# P6_V5.net
KiCad netlist of a schematic drawn in EAGLE
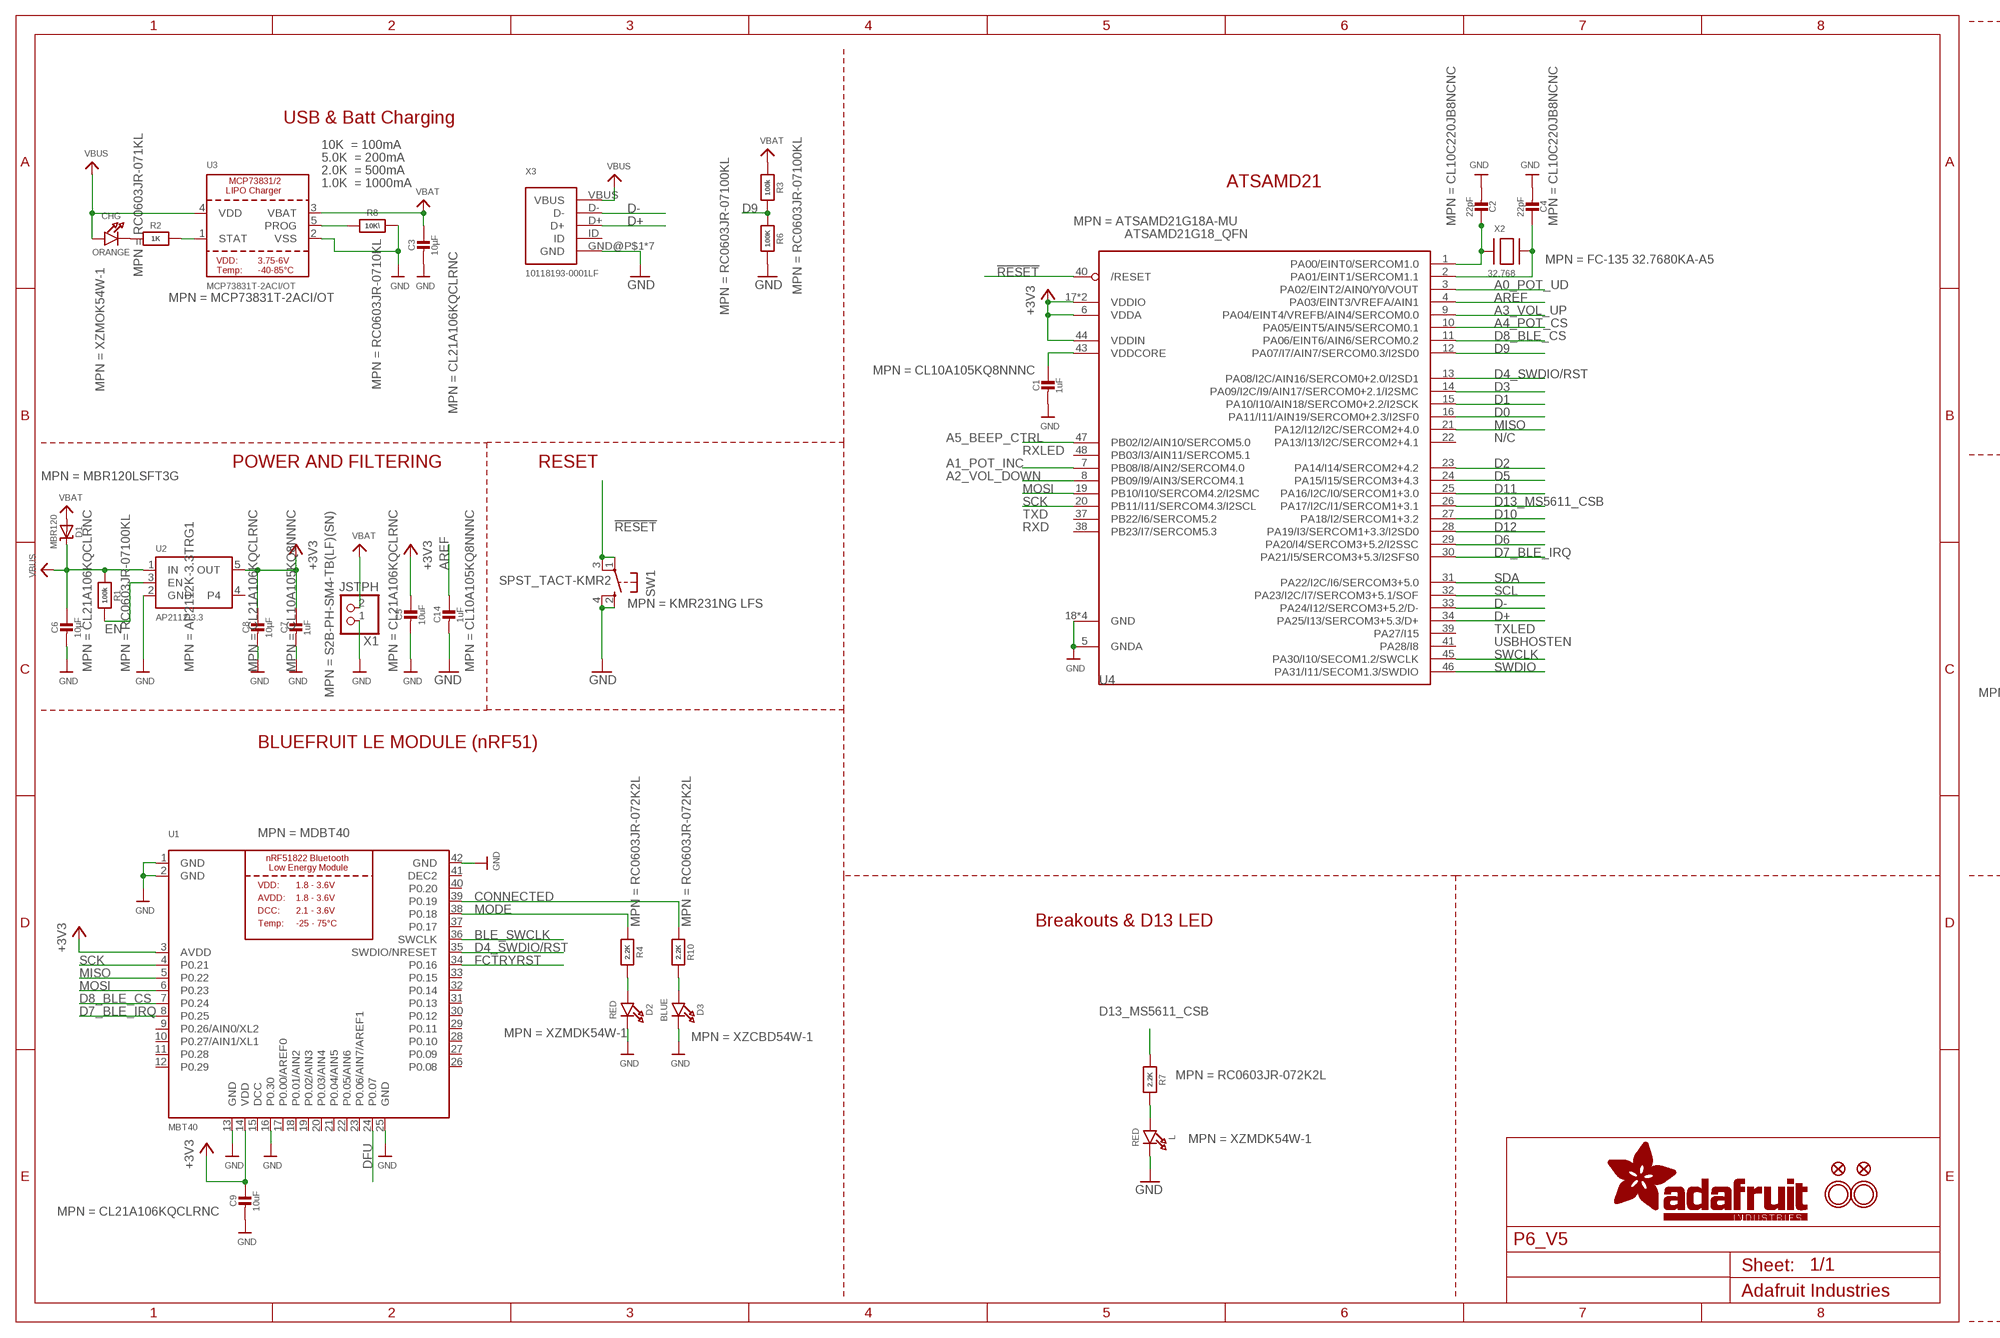
[diagram p0: schematic, sheet 1, part 1 of 2]
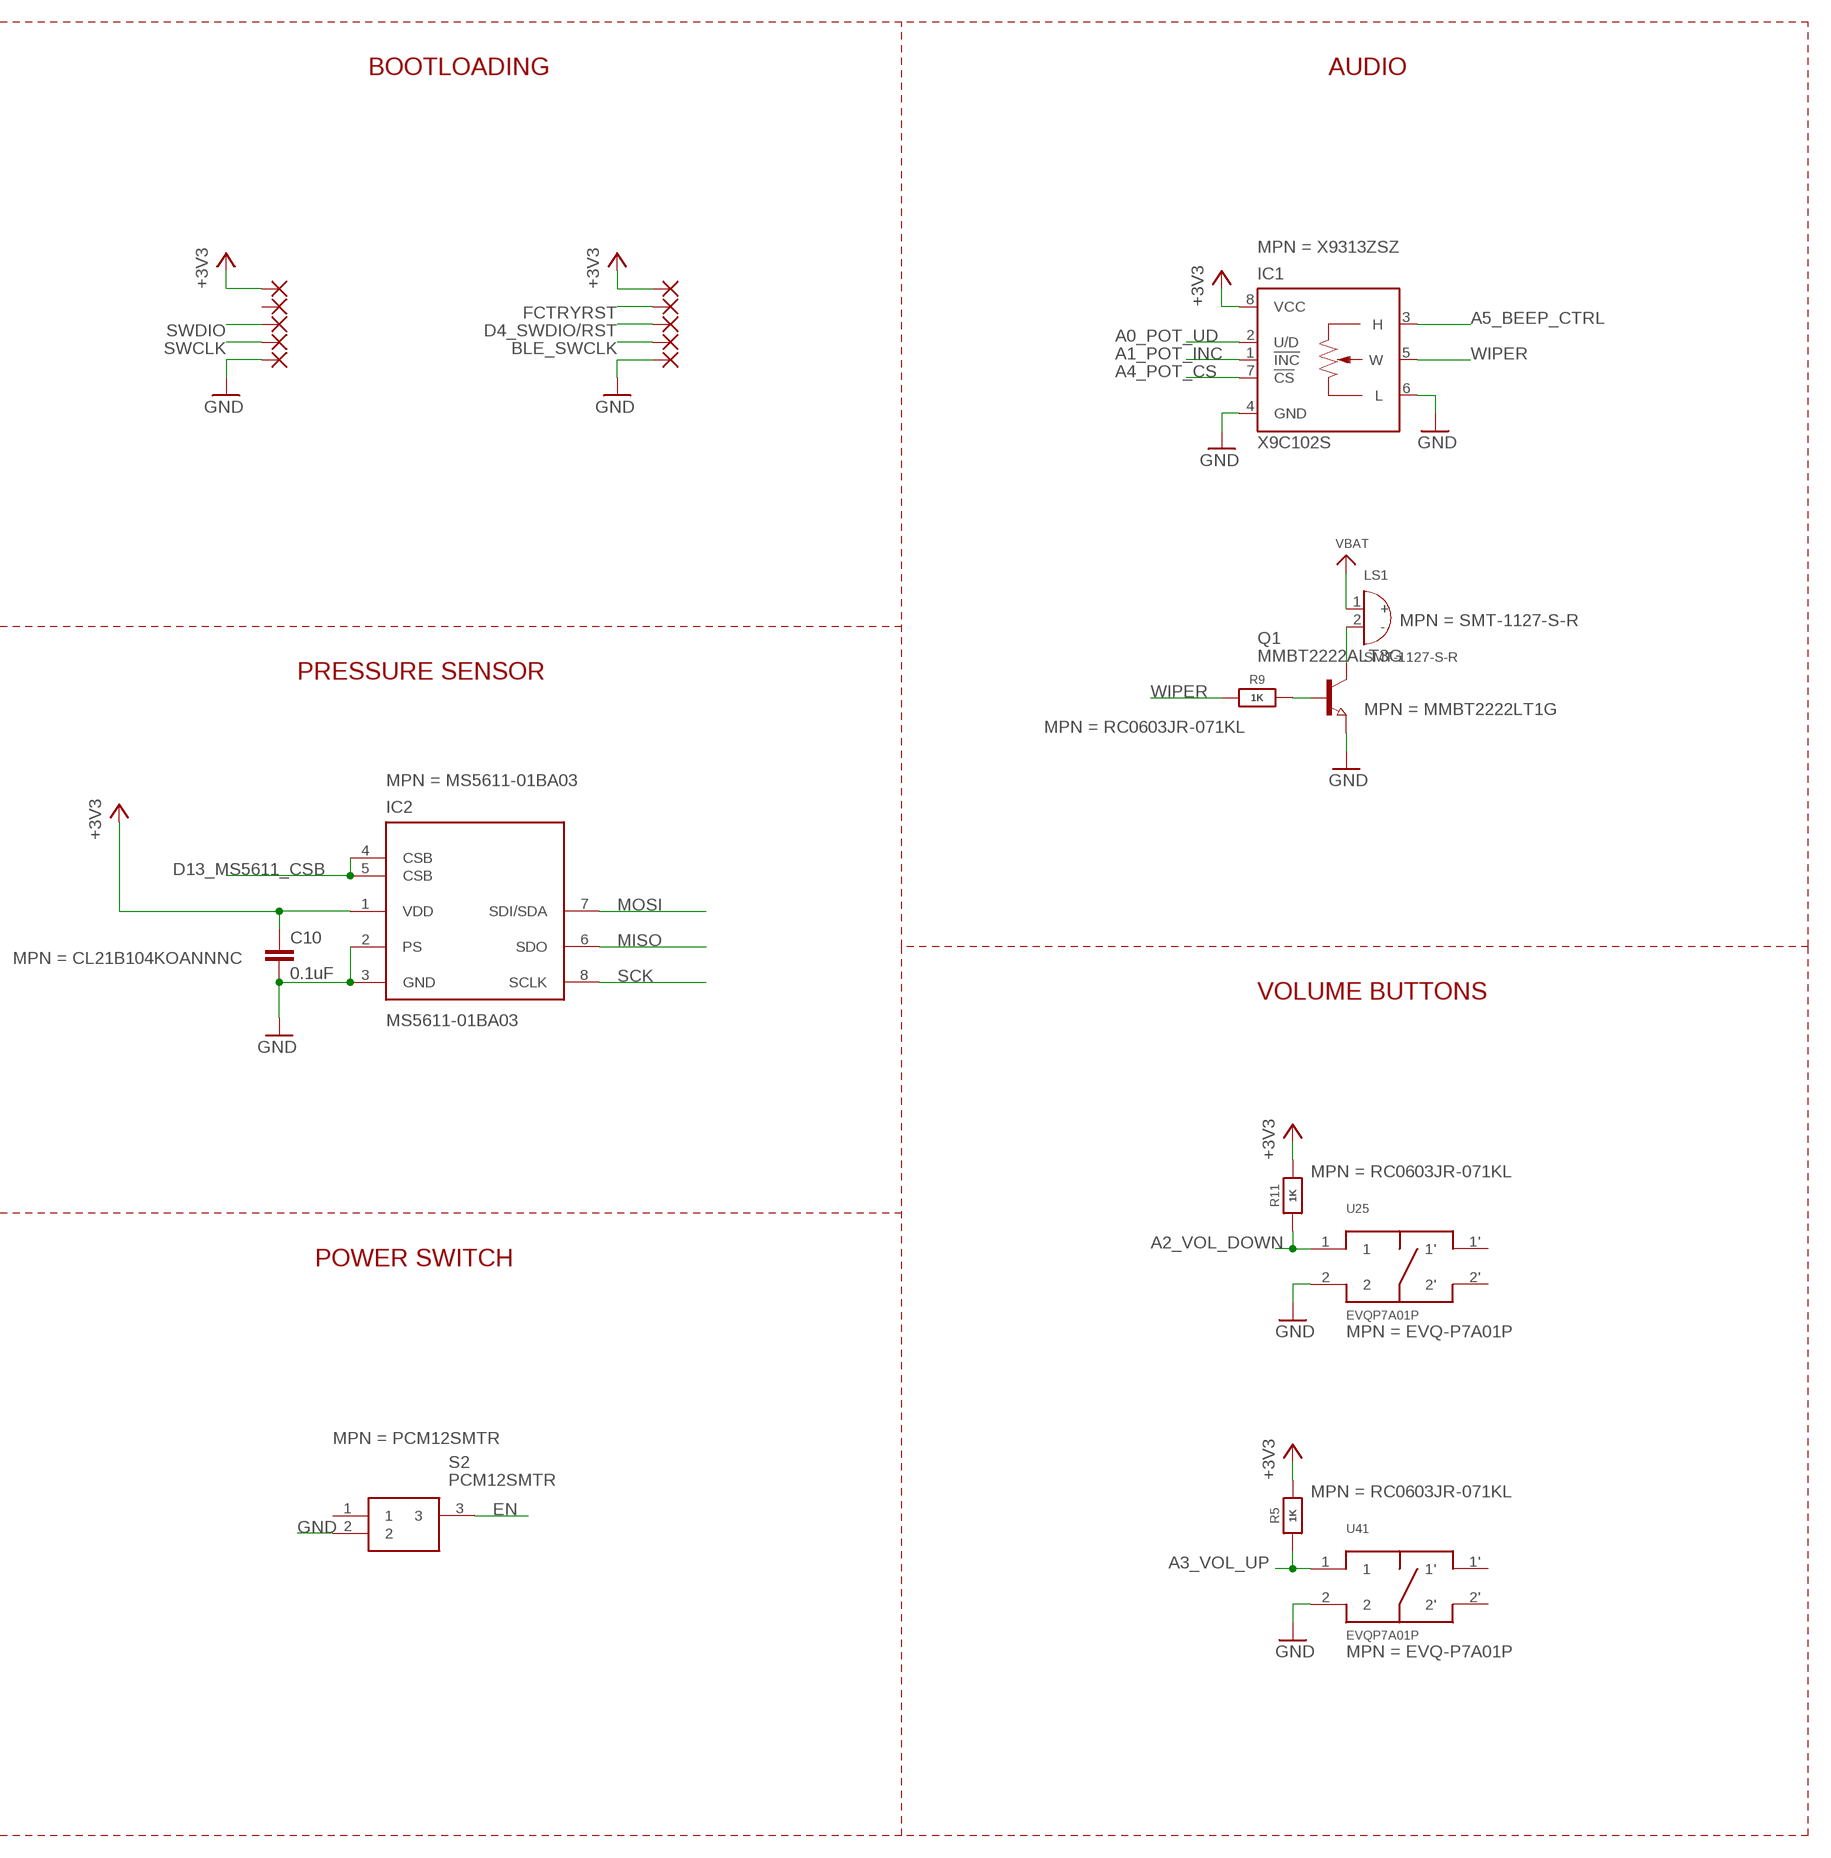
[diagram p1: schematic, sheet 1, part 2 of 2]

(export (version "E")
  (design (tool "Eeschema 10.0.6"))
  (components
    (comp (ref "C1")
      (value "1uF")
      (footprint "eagle-import:0603-NO")
      (fields (field (name "MPN") "CL10A105KQ8NNNC"))
      (libsource (lib "eagle-import") (part "CAP_CERAMIC0603_NO"))
    )
    (comp (ref "C2")
      (value "22pF")
      (footprint "eagle-import:0603-NO")
      (fields (field (name "MPN") "CL10C220JB8NCNC"))
      (libsource (lib "eagle-import") (part "CAP_CERAMIC0603_NO"))
    )
    (comp (ref "C3")
      (value "10µF")
      (footprint "eagle-import:0805-NO")
      (fields (field (name "MPN") "CL21A106KQCLRNC"))
      (libsource (lib "eagle-import") (part "CAP_CERAMIC0805-NOOUTLINE"))
    )
    (comp (ref "C4")
      (value "22pF")
      (footprint "eagle-import:0603-NO")
      (fields (field (name "MPN") "CL10C220JB8NCNC"))
      (libsource (lib "eagle-import") (part "CAP_CERAMIC0603_NO"))
    )
    (comp (ref "C5")
      (value "10uF")
      (footprint "eagle-import:0805-NO")
      (fields (field (name "MPN") "CL21A106KQCLRNC"))
      (libsource (lib "eagle-import") (part "CAP_CERAMIC0805-NOOUTLINE"))
    )
    (comp (ref "C6")
      (value "10µF")
      (footprint "eagle-import:0805-NO")
      (fields (field (name "MPN") "CL21A106KQCLRNC"))
      (libsource (lib "eagle-import") (part "CAP_CERAMIC0805-NOOUTLINE"))
    )
    (comp (ref "C7")
      (value "1uF")
      (footprint "eagle-import:0603-NO")
      (fields (field (name "MPN") "CL10A105KQ8NNNC"))
      (libsource (lib "eagle-import") (part "CAP_CERAMIC0603_NO"))
    )
    (comp (ref "C8")
      (value "10µF")
      (footprint "eagle-import:0805-NO")
      (fields (field (name "MPN") "CL21A106KQCLRNC"))
      (libsource (lib "eagle-import") (part "CAP_CERAMIC0805-NOOUTLINE"))
    )
    (comp (ref "C9")
      (value "10uF")
      (footprint "eagle-import:0805-NO")
      (fields (field (name "MPN") "CL21A106KQCLRNC"))
      (libsource (lib "eagle-import") (part "CAP_CERAMIC0805-NOOUTLINE"))
    )
    (comp (ref "C10")
      (value "0.1uF")
      (footprint "eagle-import:C0805K")
      (fields (field (name "MPN") "CL21B104KOANNNC"))
      (libsource (lib "eagle-import") (part "C-EUC0805K"))
    )
    (comp (ref "C14")
      (value "1uF")
      (footprint "eagle-import:0603-NO")
      (fields (field (name "MPN") "CL10A105KQ8NNNC"))
      (libsource (lib "eagle-import") (part "CAP_CERAMIC0603_NO"))
    )
    (comp (ref "CHG")
      (value "ORANGE")
      (footprint "eagle-import:CHIPLED_0805_NOOUTLINE")
      (fields (field (name "MPN") "XZMOK54W-1"))
      (libsource (lib "eagle-import") (part "LED0805_NOOUTLINE"))
    )
    (comp (ref "D1")
      (value "MBR120")
      (footprint "eagle-import:SOD-123")
      (fields (field (name "MPN") "MBR120LSFT3G"))
      (libsource (lib "eagle-import") (part "DIODE-SCHOTTKYSOD-123"))
    )
    (comp (ref "D2")
      (value "RED")
      (footprint "eagle-import:CHIPLED_0805_NOOUTLINE")
      (fields (field (name "MPN") "XZMDK54W-1"))
      (libsource (lib "eagle-import") (part "LED0805_NOOUTLINE"))
    )
    (comp (ref "D3")
      (value "BLUE")
      (footprint "eagle-import:CHIPLED_0805_NOOUTLINE")
      (fields (field (name "MPN") "XZCBD54W-1"))
      (libsource (lib "eagle-import") (part "LED0805_NOOUTLINE"))
    )
    (comp (ref "IC1")
      (value "X9C102S")
      (footprint "eagle-import:SOIC08")
      (fields
        (field (name "MF") "INTERSIL")
        (field (name "MPN") "X9C102SIZ")
        (field (name "MPN_1") "X9313ZSZ")
      )
      (libsource (lib "eagle-import") (part "X9C102S"))
    )
    (comp (ref "IC2")
      (value "MS5611-01BA03")
      (footprint "eagle-import:SON125P300X500X100-8N")
      (fields (field (name "MPN") "MS5611-01BA03"))
      (libsource (lib "eagle-import") (part "MS5611-01BA03UNO"))
    )
    (comp (ref "L")
      (value "RED")
      (footprint "eagle-import:CHIPLED_0805_NOOUTLINE")
      (fields (field (name "MPN") "XZMDK54W-1"))
      (libsource (lib "eagle-import") (part "LED0805_NOOUTLINE"))
    )
    (comp (ref "LS1")
      (value "SMT-1127-S-R")
      (footprint "eagle-import:XDCR_SMT-1127-S-R")
      (description "Black Passive Electromagnetic SMD Buzzer 3V 80mA 2700Hz 92dB 9x3.2mm")
      (fields
        (field (name "MF") "PUI Audio")
        (field (name "MP") "BOT-03D-BUJEON, SMT-1127-S-R")
        (field (name "MPN") "SMT-1127-S-R")
      )
      (libsource (lib "eagle-import") (part "SMT-1127-S-R"))
    )
    (comp (ref "PAD1")
      (value "1,6/0,8")
      (footprint "eagle-import:1,6_0,8")
      (libsource (lib "eagle-import") (part "1,6/0,8"))
    )
    (comp (ref "PAD2")
      (value "1,6/0,8")
      (footprint "eagle-import:1,6_0,8")
      (libsource (lib "eagle-import") (part "1,6/0,8"))
    )
    (comp (ref "PAD3")
      (value "1,6/0,8")
      (footprint "eagle-import:1,6_0,8")
      (libsource (lib "eagle-import") (part "1,6/0,8"))
    )
    (comp (ref "PAD4")
      (value "1,6/0,8")
      (footprint "eagle-import:1,6_0,8")
      (libsource (lib "eagle-import") (part "1,6/0,8"))
    )
    (comp (ref "PAD5")
      (value "1,6/0,8")
      (footprint "eagle-import:1,6_0,8")
      (libsource (lib "eagle-import") (part "1,6/0,8"))
    )
    (comp (ref "PAD6")
      (value "1,6/0,8")
      (footprint "eagle-import:1,6_0,8")
      (libsource (lib "eagle-import") (part "1,6/0,8"))
    )
    (comp (ref "PAD7")
      (value "1,6/0,8")
      (footprint "eagle-import:1,6_0,8")
      (libsource (lib "eagle-import") (part "1,6/0,8"))
    )
    (comp (ref "PAD8")
      (value "1,6/0,8")
      (footprint "eagle-import:1,6_0,8")
      (libsource (lib "eagle-import") (part "1,6/0,8"))
    )
    (comp (ref "PAD9")
      (value "1,6/0,8")
      (footprint "eagle-import:1,6_0,8")
      (libsource (lib "eagle-import") (part "1,6/0,8"))
    )
    (comp (ref "PAD10")
      (value "1,6/0,8")
      (footprint "eagle-import:1,6_0,8")
      (libsource (lib "eagle-import") (part "1,6/0,8"))
    )
    (comp (ref "Q1")
      (value "MMBT2222ALT3G")
      (footprint "eagle-import:SOT23")
      (fields (field (name "MPN") "MMBT2222LT1G"))
      (libsource (lib "eagle-import") (part "NPN-TRANSISTOR_SOT23"))
    )
    (comp (ref "R1")
      (value "100k")
      (footprint "eagle-import:0603-NO")
      (fields (field (name "MPN") "RC0603JR-07100KL"))
      (libsource (lib "eagle-import") (part "RESISTOR_0603_NOOUT"))
    )
    (comp (ref "R2")
      (value "1K")
      (footprint "eagle-import:0603-NO")
      (fields (field (name "MPN") "RC0603JR-071KL"))
      (libsource (lib "eagle-import") (part "RESISTOR_0603_NOOUT"))
    )
    (comp (ref "R3")
      (value "100k")
      (footprint "eagle-import:0603-NO")
      (fields (field (name "MPN") "RC0603JR-07100KL"))
      (libsource (lib "eagle-import") (part "RESISTOR_0603_NOOUT"))
    )
    (comp (ref "R4")
      (value "2.2K")
      (footprint "eagle-import:0603-NO")
      (fields (field (name "MPN") "RC0603JR-072K2L"))
      (libsource (lib "eagle-import") (part "RESISTOR_0603_NOOUT"))
    )
    (comp (ref "R5")
      (value "1K")
      (footprint "eagle-import:0603-NO")
      (fields (field (name "MPN") "RC0603JR-071KL"))
      (libsource (lib "eagle-import") (part "RESISTOR_0603_NOOUT"))
    )
    (comp (ref "R6")
      (value "100K")
      (footprint "eagle-import:0603-NO")
      (fields (field (name "MPN") "RC0603JR-07100KL"))
      (libsource (lib "eagle-import") (part "RESISTOR_0603_NOOUT"))
    )
    (comp (ref "R7")
      (value "2.2K")
      (footprint "eagle-import:0603-NO")
      (fields (field (name "MPN") "RC0603JR-072K2L"))
      (libsource (lib "eagle-import") (part "RESISTOR_0603_NOOUT"))
    )
    (comp (ref "R8")
      (value "10K\\")
      (footprint "eagle-import:0603-NO")
      (fields (field (name "MPN") "RC0603JR-0710KL"))
      (libsource (lib "eagle-import") (part "RESISTOR_0603_NOOUT"))
    )
    (comp (ref "R9")
      (value "1K")
      (footprint "eagle-import:0603-NO")
      (fields (field (name "MPN") "RC0603JR-071KL"))
      (libsource (lib "eagle-import") (part "RESISTOR_0603_NOOUT"))
    )
    (comp (ref "R10")
      (value "2.2K")
      (footprint "eagle-import:0603-NO")
      (fields (field (name "MPN") "RC0603JR-072K2L"))
      (libsource (lib "eagle-import") (part "RESISTOR_0603_NOOUT"))
    )
    (comp (ref "R11")
      (value "1K")
      (footprint "eagle-import:0603-NO")
      (fields (field (name "MPN") "RC0603JR-071KL"))
      (libsource (lib "eagle-import") (part "RESISTOR_0603_NOOUT"))
    )
    (comp (ref "S2")
      (value "PCM12SMTR")
      (footprint "eagle-import:PCM12SMTR_1")
      (fields (field (name "RS_PART_NUMBER") "7931721P") (field (name "MPN") "PCM12SMTR"))
      (libsource (lib "eagle-import") (part "PCM12SMTR"))
    )
    (comp (ref "SW1")
      (value "SPST_TACT-KMR2")
      (footprint "eagle-import:KMR2")
      (fields (field (name "MPN") "KMR231NG LFS"))
      (libsource (lib "eagle-import") (part "SPST_TACT-KMR2"))
    )
    (comp (ref "U$31")
      (value "MOUNTINGHOLE2.5")
      (footprint "eagle-import:MOUNTINGHOLE_2.5_PLATED")
      (libsource (lib "eagle-import") (part "MOUNTINGHOLE2.5"))
    )
    (comp (ref "U$32")
      (value "MOUNTINGHOLE2.5")
      (footprint "eagle-import:MOUNTINGHOLE_2.5_PLATED")
      (libsource (lib "eagle-import") (part "MOUNTINGHOLE2.5"))
    )
    (comp (ref "U$34")
      (value "FIDUCIAL\"\"")
      (footprint "eagle-import:FIDUCIAL_1MM")
      (libsource (lib "eagle-import") (part "FIDUCIAL{dblquote}{dblquote}"))
    )
    (comp (ref "U$35")
      (value "FIDUCIAL\"\"")
      (footprint "eagle-import:FIDUCIAL_1MM")
      (libsource (lib "eagle-import") (part "FIDUCIAL{dblquote}{dblquote}"))
    )
    (comp (ref "U1")
      (value "MBT40")
      (footprint "eagle-import:BLE_MODULE_RAYTAC_MDBT40")
      (fields (field (name "MPN") "MDBT40"))
      (libsource (lib "eagle-import") (part "NRF51822_MODULE_MDBT40"))
    )
    (comp (ref "U2")
      (value "AP2112-3.3")
      (footprint "eagle-import:SOT23-5")
      (fields (field (name "MPN") "AP2112K-3.3TRG1"))
      (libsource (lib "eagle-import") (part "VREG_SOT23-5"))
    )
    (comp (ref "U3")
      (value "MCP73831T-2ACI/OT")
      (footprint "eagle-import:SOT23-5")
      (fields (field (name "MPN") "MCP73831T-2ACI/OT"))
      (libsource (lib "eagle-import") (part "MCP73831/2"))
    )
    (comp (ref "U4")
      (value "ATSAMD21G18_QFN")
      (footprint "eagle-import:TQFN48_7MM")
      (fields (field (name "MPN") "ATSAMD21G18A-MU"))
      (libsource (lib "eagle-import") (part "ATSAMD21J_QFN"))
    )
    (comp (ref "U25")
      (value "EVQP7A01P")
      (footprint "eagle-import:EVQP7A01P")
      (fields (field (name "MPN") "EVQ-P7A01P"))
      (libsource (lib "eagle-import") (part "EVQP7A01P"))
    )
    (comp (ref "U41")
      (value "EVQP7A01P")
      (footprint "eagle-import:EVQP7A01P")
      (fields (field (name "MPN") "EVQ-P7A01P"))
      (libsource (lib "eagle-import") (part "EVQP7A01P"))
    )
    (comp (ref "X1")
      (value "JSTPH")
      (footprint "eagle-import:JSTPH2")
      (fields (field (name "MPN") "S2B-PH-SM4-TB(LF)(SN)"))
      (libsource (lib "eagle-import") (part "CON_JST_PH_2PIN"))
    )
    (comp (ref "X2")
      (value "32.768")
      (footprint "eagle-import:XTAL3215")
      (fields (field (name "MPN") "FC-135 32.7680KA-A5"))
      (libsource (lib "eagle-import") (part "XTAL-3.2X1.5"))
    )
    (comp (ref "X3")
      (value "10118193-0001LF")
      (footprint "eagle-import:10118193-0001LF")
      (libsource (lib "eagle-import") (part "10118193-0001LF"))
    )
  )
  (nets
    (net (code "1") (name "+3V3") (class "Default")
      (node (ref "C10") (pin "1") (pinfunction "1_1") (pintype "passive"))
      (node (ref "C5") (pin "1") (pinfunction "1_1") (pintype "passive"))
      (node (ref "C7") (pin "1") (pinfunction "1_1") (pintype "passive"))
      (node (ref "C8") (pin "1") (pinfunction "1_1") (pintype "passive"))
      (node (ref "C9") (pin "1") (pinfunction "1_1") (pintype "passive"))
      (node (ref "IC1") (pin "8") (pinfunction "VCC_8") (pintype "power_in"))
      (node (ref "IC2") (pin "1") (pinfunction "VDD_1") (pintype "power_in"))
      (node (ref "PAD2") (pin "1") (pinfunction "P_1") (pintype "passive"))
      (node (ref "PAD6") (pin "1") (pinfunction "P_1") (pintype "passive"))
      (node (ref "R11") (pin "2") (pinfunction "2_2") (pintype "passive"))
      (node (ref "R5") (pin "2") (pinfunction "2_2") (pintype "passive"))
      (node (ref "U1") (pin "14") (pinfunction "VDD_14") (pintype "power_in"))
      (node (ref "U1") (pin "3") (pinfunction "AVDD_3") (pintype "power_in"))
      (node (ref "U2") (pin "5") (pinfunction "OUT_5") (pintype "power_in"))
      (node (ref "U4") (pin "17") (pinfunction "VDDIO_17") (pintype "power_in"))
      (node (ref "U4") (pin "36") (pinfunction "VDDIO_36") (pintype "power_in"))
      (node (ref "U4") (pin "44") (pinfunction "VDDIN_44") (pintype "power_in"))
      (node (ref "U4") (pin "6") (pinfunction "VDDA_6") (pintype "power_in"))
    )
    (net (code "2") (name "/A0_POT_UD") (class "Default")
      (node (ref "IC1") (pin "2") (pinfunction "U/D_2") (pintype "input"))
      (node (ref "U4") (pin "3") (pinfunction "PA02/EINT2/AIN0/Y0/VOUT_3") (pintype "bidirectional"))
    )
    (net (code "3") (name "/A1_POT_INC") (class "Default")
      (node (ref "IC1") (pin "1") (pinfunction "~{INC}_1") (pintype "input"))
      (node (ref "U4") (pin "7") (pinfunction "PB08/I8/AIN2/SERCOM4.0_7") (pintype "bidirectional"))
    )
    (net (code "4") (name "/A2_VOL_DOWN") (class "Default")
      (node (ref "R11") (pin "1") (pinfunction "1_1") (pintype "passive"))
      (node (ref "U25") (pin "1") (pinfunction "1_1") (pintype "bidirectional"))
      (node (ref "U4") (pin "8") (pinfunction "PB09/I9/AIN3/SERCOM4.1_8") (pintype "bidirectional"))
    )
    (net (code "5") (name "/A3_VOL_UP") (class "Default")
      (node (ref "R5") (pin "1") (pinfunction "1_1") (pintype "passive"))
      (node (ref "U4") (pin "9") (pinfunction "PA04/EINT4/VREFB/AIN4/SERCOM0.0_9") (pintype "bidirectional"))
      (node (ref "U41") (pin "1") (pinfunction "1_1") (pintype "bidirectional"))
    )
    (net (code "6") (name "/A4_POT_CS") (class "Default")
      (node (ref "IC1") (pin "7") (pinfunction "~{CS}_7") (pintype "input"))
      (node (ref "U4") (pin "10") (pinfunction "PA05/EINT5/AIN5/SERCOM0.1_10") (pintype "bidirectional"))
    )
    (net (code "7") (name "/A5_BEEP_CTRL") (class "Default")
      (node (ref "IC1") (pin "3") (pinfunction "H_3") (pintype "passive"))
      (node (ref "U4") (pin "47") (pinfunction "PB02/I2/AIN10/SERCOM5.0_47") (pintype "bidirectional"))
    )
    (net (code "8") (name "/AREF") (class "Default")
      (node (ref "C14") (pin "1") (pinfunction "1_1") (pintype "passive"))
      (node (ref "U4") (pin "4") (pinfunction "PA03/EINT3/VREFA/AIN1_4") (pintype "bidirectional"))
    )
    (net (code "9") (name "/BLE_SWCLK") (class "Default")
      (node (ref "PAD9") (pin "1") (pinfunction "P_1") (pintype "passive"))
      (node (ref "U1") (pin "36") (pinfunction "SWCLK_36") (pintype "bidirectional"))
    )
    (net (code "10") (name "/CONNECTED") (class "Default")
      (node (ref "R10") (pin "1") (pinfunction "1_1") (pintype "passive"))
      (node (ref "U1") (pin "39") (pinfunction "P0.19_39") (pintype "bidirectional"))
    )
    (net (code "11") (name "/D+") (class "Default")
      (node (ref "U4") (pin "34") (pinfunction "PA25/I13/SERCOM3+5.3/D+_34") (pintype "bidirectional"))
      (node (ref "X3") (pin "D+") (pinfunction "D+_D+") (pintype "bidirectional"))
    )
    (net (code "12") (name "/D-") (class "Default")
      (node (ref "U4") (pin "33") (pinfunction "PA24/I12/SERCOM3+5.2/D-_33") (pintype "bidirectional"))
      (node (ref "X3") (pin "D-") (pinfunction "D-_D-") (pintype "bidirectional"))
    )
    (net (code "13") (name "/D0") (class "Default")
      (node (ref "U4") (pin "16") (pinfunction "PA11/I11/AIN19/SERCOM0+2.3/I2SF0_16") (pintype "bidirectional"))
    )
    (net (code "14") (name "/D1") (class "Default")
      (node (ref "U4") (pin "15") (pinfunction "PA10/I10/AIN18/SERCOM0+2.2/I2SCK_15") (pintype "bidirectional"))
    )
    (net (code "15") (name "/D2") (class "Default")
      (node (ref "U4") (pin "23") (pinfunction "PA14/I14/SERCOM2+4.2_23") (pintype "bidirectional"))
    )
    (net (code "16") (name "/D3") (class "Default")
      (node (ref "U4") (pin "14") (pinfunction "PA09/I2C/I9/AIN17/SERCOM0+2.1/I2SMC_14") (pintype "bidirectional"))
    )
    (net (code "17") (name "/D4_SWDIO{slash}RST") (class "Default")
      (node (ref "PAD8") (pin "1") (pinfunction "P_1") (pintype "passive"))
      (node (ref "U1") (pin "35") (pinfunction "SWDIO/NRESET_35") (pintype "bidirectional"))
      (node (ref "U4") (pin "13") (pinfunction "PA08/I2C/AIN16/SERCOM0+2.0/I2SD1_13") (pintype "bidirectional"))
    )
    (net (code "18") (name "/D5") (class "Default")
      (node (ref "U4") (pin "24") (pinfunction "PA15/I15/SERCOM3+4.3_24") (pintype "bidirectional"))
    )
    (net (code "19") (name "/D6") (class "Default")
      (node (ref "U4") (pin "29") (pinfunction "PA20/I4/SERCOM3+5.2/I2SSC_29") (pintype "bidirectional"))
    )
    (net (code "20") (name "/D7_BLE_IRQ") (class "Default")
      (node (ref "U1") (pin "8") (pinfunction "P0.25_8") (pintype "bidirectional"))
      (node (ref "U4") (pin "30") (pinfunction "PA21/I5/SERCOM3+5.3/I2SFS0_30") (pintype "bidirectional"))
    )
    (net (code "21") (name "/D8_BLE_CS") (class "Default")
      (node (ref "U1") (pin "7") (pinfunction "P0.24_7") (pintype "bidirectional"))
      (node (ref "U4") (pin "11") (pinfunction "PA06/EINT6/AIN6/SERCOM0.2_11") (pintype "bidirectional"))
    )
    (net (code "22") (name "/D9") (class "Default")
      (node (ref "R3") (pin "2") (pinfunction "2_2") (pintype "passive"))
      (node (ref "R6") (pin "1") (pinfunction "1_1") (pintype "passive"))
      (node (ref "U4") (pin "12") (pinfunction "PA07/I7/AIN7/SERCOM0.3/I2SD0_12") (pintype "bidirectional"))
    )
    (net (code "23") (name "/D10") (class "Default")
      (node (ref "U4") (pin "27") (pinfunction "PA18/I2/SERCOM1+3.2_27") (pintype "bidirectional"))
    )
    (net (code "24") (name "/D11") (class "Default")
      (node (ref "U4") (pin "25") (pinfunction "PA16/I2C/I0/SERCOM1+3.0_25") (pintype "bidirectional"))
    )
    (net (code "25") (name "/D12") (class "Default")
      (node (ref "U4") (pin "28") (pinfunction "PA19/I3/SERCOM1+3.3/I2SD0_28") (pintype "bidirectional"))
    )
    (net (code "26") (name "/D13_MS5611_CSB") (class "Default")
      (node (ref "IC2") (pin "4") (pinfunction "CSB_4") (pintype "input"))
      (node (ref "IC2") (pin "5") (pinfunction "CSB_5") (pintype "input"))
      (node (ref "R7") (pin "1") (pinfunction "1_1") (pintype "passive"))
      (node (ref "U4") (pin "26") (pinfunction "PA17/I2C/I1/SERCOM1+3.1_26") (pintype "bidirectional"))
    )
    (net (code "27") (name "/DCC") (class "Default")
      (node (ref "U1") (pin "15") (pinfunction "DCC_15") (pintype "power_in"))
    )
    (net (code "28") (name "/DEC2") (class "Default")
      (node (ref "U1") (pin "41") (pinfunction "DEC2_41") (pintype "power_in"))
    )
    (net (code "29") (name "/DFU") (class "Default")
      (node (ref "U1") (pin "24") (pinfunction "P0.07_24") (pintype "bidirectional"))
    )
    (net (code "30") (name "/EN") (class "Default")
      (node (ref "R1") (pin "2") (pinfunction "2_2") (pintype "passive"))
      (node (ref "S2") (pin "3") (pinfunction "3_3") (pintype "input"))
      (node (ref "U2") (pin "3") (pinfunction "EN_3") (pintype "input"))
    )
    (net (code "31") (name "/FCTRYRST") (class "Default")
      (node (ref "PAD7") (pin "1") (pinfunction "P_1") (pintype "passive"))
      (node (ref "U1") (pin "34") (pinfunction "P0.16_34") (pintype "bidirectional"))
    )
    (net (code "32") (name "/MISO") (class "Default")
      (node (ref "IC2") (pin "6") (pinfunction "SDO_6") (pintype "output"))
      (node (ref "U1") (pin "5") (pinfunction "P0.22_5") (pintype "bidirectional"))
      (node (ref "U4") (pin "21") (pinfunction "PA12/I12/I2C/SERCOM2+4.0_21") (pintype "bidirectional"))
    )
    (net (code "33") (name "/MODE") (class "Default")
      (node (ref "R4") (pin "1") (pinfunction "1_1") (pintype "passive"))
      (node (ref "U1") (pin "38") (pinfunction "P0.18_38") (pintype "bidirectional"))
    )
    (net (code "34") (name "/MOSI") (class "Default")
      (node (ref "IC2") (pin "7") (pinfunction "SDI/SDA_7") (pintype "bidirectional"))
      (node (ref "U1") (pin "6") (pinfunction "P0.23_6") (pintype "bidirectional"))
      (node (ref "U4") (pin "19") (pinfunction "PB10/I10/SERCOM4.2/I2SMC_19") (pintype "bidirectional"))
    )
    (net (code "35") (name "/SCK") (class "Default")
      (node (ref "IC2") (pin "8") (pinfunction "SCLK_8") (pintype "input"))
      (node (ref "U1") (pin "4") (pinfunction "P0.21_4") (pintype "bidirectional"))
      (node (ref "U4") (pin "20") (pinfunction "PB11/I11/SERCOM4.3/I2SCL_20") (pintype "bidirectional"))
    )
    (net (code "36") (name "/SCL") (class "Default")
      (node (ref "U4") (pin "32") (pinfunction "PA23/I2C/I7/SERCOM3+5.1/SOF_32") (pintype "bidirectional"))
    )
    (net (code "37") (name "/SDA") (class "Default")
      (node (ref "U4") (pin "31") (pinfunction "PA22/I2C/I6/SERCOM3+5.0_31") (pintype "bidirectional"))
    )
    (net (code "38") (name "/SWCLK") (class "Default")
      (node (ref "PAD4") (pin "1") (pinfunction "P_1") (pintype "passive"))
      (node (ref "U4") (pin "45") (pinfunction "PA30/I10/SECOM1.2/SWCLK_45") (pintype "bidirectional"))
    )
    (net (code "39") (name "/SWDIO") (class "Default")
      (node (ref "PAD3") (pin "1") (pinfunction "P_1") (pintype "passive"))
      (node (ref "U4") (pin "46") (pinfunction "PA31/I11/SECOM1.3/SWDIO_46") (pintype "bidirectional"))
    )
    (net (code "40") (name "/WIPER") (class "Default")
      (node (ref "IC1") (pin "5") (pinfunction "W_5") (pintype "passive"))
      (node (ref "R9") (pin "1") (pinfunction "1_1") (pintype "passive"))
    )
    (net (code "41") (name "/~{RESET}") (class "Default")
      (node (ref "SW1") (pin "1") (pinfunction "P_1") (pintype "passive"))
      (node (ref "SW1") (pin "3") (pinfunction "P1_3") (pintype "passive"))
      (node (ref "U4") (pin "40") (pinfunction "/RESET_40") (pintype "bidirectional"))
    )
    (net (code "42") (name "GND") (class "Default")
      (node (ref "C1") (pin "2") (pinfunction "2_2") (pintype "passive"))
      (node (ref "C10") (pin "2") (pinfunction "2_2") (pintype "passive"))
      (node (ref "C14") (pin "2") (pinfunction "2_2") (pintype "passive"))
      (node (ref "C2") (pin "2") (pinfunction "2_2") (pintype "passive"))
      (node (ref "C3") (pin "2") (pinfunction "2_2") (pintype "passive"))
      (node (ref "C4") (pin "2") (pinfunction "2_2") (pintype "passive"))
      (node (ref "C5") (pin "2") (pinfunction "2_2") (pintype "passive"))
      (node (ref "C6") (pin "2") (pinfunction "2_2") (pintype "passive"))
      (node (ref "C7") (pin "2") (pinfunction "2_2") (pintype "passive"))
      (node (ref "C8") (pin "2") (pinfunction "2_2") (pintype "passive"))
      (node (ref "C9") (pin "2") (pinfunction "2_2") (pintype "passive"))
      (node (ref "D2") (pin "C") (pinfunction "C_C") (pintype "passive"))
      (node (ref "D3") (pin "C") (pinfunction "C_C") (pintype "passive"))
      (node (ref "IC1") (pin "4") (pinfunction "GND_4") (pintype "power_in"))
      (node (ref "IC1") (pin "6") (pinfunction "L_6") (pintype "passive"))
      (node (ref "IC2") (pin "2") (pinfunction "PS_2") (pintype "input"))
      (node (ref "IC2") (pin "3") (pinfunction "GND_3") (pintype "power_in"))
      (node (ref "L") (pin "C") (pinfunction "C_C") (pintype "passive"))
      (node (ref "PAD10") (pin "1") (pinfunction "P_1") (pintype "passive"))
      (node (ref "PAD5") (pin "1") (pinfunction "P_1") (pintype "passive"))
      (node (ref "Q1") (pin "2") (pinfunction "E_2") (pintype "passive"))
      (node (ref "R6") (pin "2") (pinfunction "2_2") (pintype "passive"))
      (node (ref "R8") (pin "2") (pinfunction "2_2") (pintype "passive"))
      (node (ref "S2") (pin "2") (pinfunction "2_2") (pintype "input"))
      (node (ref "SW1") (pin "2") (pinfunction "S_2") (pintype "passive"))
      (node (ref "SW1") (pin "4") (pinfunction "S1_4") (pintype "passive"))
      (node (ref "U1") (pin "1") (pinfunction "GND_1") (pintype "power_in"))
      (node (ref "U1") (pin "13") (pinfunction "GND_13") (pintype "power_in"))
      (node (ref "U1") (pin "16") (pinfunction "P0.30_16") (pintype "bidirectional"))
      (node (ref "U1") (pin "2") (pinfunction "GND_2") (pintype "power_in"))
      (node (ref "U1") (pin "25") (pinfunction "GND_25") (pintype "power_in"))
      (node (ref "U1") (pin "42") (pinfunction "GND_42") (pintype "power_in"))
      (node (ref "U2") (pin "2") (pinfunction "GND_2") (pintype "power_in"))
      (node (ref "U25") (pin "2") (pinfunction "2_2") (pintype "bidirectional"))
      (node (ref "U3") (pin "2") (pinfunction "VSS_2") (pintype "power_in"))
      (node (ref "U4") (pin "18") (pinfunction "GND_18") (pintype "power_in"))
      (node (ref "U4") (pin "35") (pinfunction "GND_35") (pintype "power_in"))
      (node (ref "U4") (pin "42") (pinfunction "GND_42") (pintype "power_in"))
      (node (ref "U4") (pin "5") (pinfunction "GNDA_5") (pintype "power_in"))
      (node (ref "U4") (pin "THERMAL") (pinfunction "GND_THERMAL") (pintype "power_in"))
      (node (ref "U41") (pin "2") (pinfunction "2_2") (pintype "bidirectional"))
      (node (ref "X1") (pin "1") (pinfunction "1_1") (pintype "passive"))
      (node (ref "X3") (pin "GND@P$1") (pinfunction "GND_GND@P$1") (pintype "bidirectional"))
      (node (ref "X3") (pin "GND@P$2") (pinfunction "GND_GND@P$2") (pintype "bidirectional"))
      (node (ref "X3") (pin "GND@P$5") (pinfunction "GND_GND@P$5") (pintype "bidirectional"))
      (node (ref "X3") (pin "GND@P$6") (pinfunction "GND_GND@P$6") (pintype "bidirectional"))
      (node (ref "X3") (pin "GND@P$7") (pinfunction "GND_GND@P$7") (pintype "bidirectional"))
      (node (ref "X3") (pin "GND@P$8") (pinfunction "GND_GND@P$8") (pintype "bidirectional"))
      (node (ref "X3") (pin "GND@P$9") (pinfunction "GND_GND@P$9") (pintype "bidirectional"))
    )
    (net (code "43") (name "Net-(CHG-PadC)") (class "Default")
      (node (ref "CHG") (pin "C") (pinfunction "C_C") (pintype "passive"))
      (node (ref "R2") (pin "1") (pinfunction "1_1") (pintype "passive"))
    )
    (net (code "44") (name "Net-(D2-PadA)") (class "Default")
      (node (ref "D2") (pin "A") (pinfunction "A_A") (pintype "passive"))
      (node (ref "R4") (pin "2") (pinfunction "2_2") (pintype "passive"))
    )
    (net (code "45") (name "Net-(D3-PadA)") (class "Default")
      (node (ref "D3") (pin "A") (pinfunction "A_A") (pintype "passive"))
      (node (ref "R10") (pin "2") (pinfunction "2_2") (pintype "passive"))
    )
    (net (code "46") (name "Net-(L-PadA)") (class "Default")
      (node (ref "L") (pin "A") (pinfunction "A_A") (pintype "passive"))
      (node (ref "R7") (pin "2") (pinfunction "2_2") (pintype "passive"))
    )
    (net (code "47") (name "Net-(LS1--)") (class "Default")
      (node (ref "LS1") (pin "2") (pinfunction "-_2") (pintype "passive"))
      (node (ref "Q1") (pin "3") (pinfunction "C_3") (pintype "passive"))
    )
    (net (code "48") (name "Net-(Q1-B)") (class "Default")
      (node (ref "Q1") (pin "1") (pinfunction "B_1") (pintype "passive"))
      (node (ref "R9") (pin "2") (pinfunction "2_2") (pintype "passive"))
    )
    (net (code "49") (name "Net-(U3-PROG)") (class "Default")
      (node (ref "R8") (pin "1") (pinfunction "1_1") (pintype "passive"))
      (node (ref "U3") (pin "5") (pinfunction "PROG_5") (pintype "input"))
    )
    (net (code "50") (name "Net-(U3-STAT)") (class "Default")
      (node (ref "R2") (pin "2") (pinfunction "2_2") (pintype "passive"))
      (node (ref "U3") (pin "1") (pinfunction "STAT_1") (pintype "output"))
    )
    (net (code "51") (name "Net-(U4-PA00{slash}EINT0{slash}SERCOM1.0)") (class "Default")
      (node (ref "C2") (pin "1") (pinfunction "1_1") (pintype "passive"))
      (node (ref "U4") (pin "1") (pinfunction "PA00/EINT0/SERCOM1.0_1") (pintype "bidirectional"))
      (node (ref "X2") (pin "P$1") (pinfunction "P$1_P$1") (pintype "bidirectional"))
    )
    (net (code "52") (name "Net-(U4-PA01{slash}EINT1{slash}SERCOM1.1)") (class "Default")
      (node (ref "C4") (pin "1") (pinfunction "1_1") (pintype "passive"))
      (node (ref "U4") (pin "2") (pinfunction "PA01/EINT1/SERCOM1.1_2") (pintype "bidirectional"))
      (node (ref "X2") (pin "P$2") (pinfunction "P$2_P$2") (pintype "bidirectional"))
    )
    (net (code "53") (name "Net-(U4-VDDCORE)") (class "Default")
      (node (ref "C1") (pin "1") (pinfunction "1_1") (pintype "passive"))
      (node (ref "U4") (pin "43") (pinfunction "VDDCORE_43") (pintype "power_in"))
    )
    (net (code "54") (name "VBAT") (class "Default")
      (node (ref "C3") (pin "1") (pinfunction "1_1") (pintype "passive"))
      (node (ref "D1") (pin "A") (pinfunction "A_A") (pintype "passive"))
      (node (ref "LS1") (pin "1") (pinfunction "+_1") (pintype "passive"))
      (node (ref "R3") (pin "1") (pinfunction "1_1") (pintype "passive"))
      (node (ref "U3") (pin "3") (pinfunction "VBAT_3") (pintype "power_in"))
      (node (ref "X1") (pin "2") (pinfunction "2_2") (pintype "passive"))
    )
    (net (code "55") (name "VBUS") (class "Default")
      (node (ref "C6") (pin "1") (pinfunction "1_1") (pintype "passive"))
      (node (ref "CHG") (pin "A") (pinfunction "A_A") (pintype "passive"))
      (node (ref "D1") (pin "C") (pinfunction "C_C") (pintype "passive"))
      (node (ref "R1") (pin "1") (pinfunction "1_1") (pintype "passive"))
      (node (ref "U2") (pin "1") (pinfunction "IN_1") (pintype "power_in"))
      (node (ref "U3") (pin "4") (pinfunction "VDD_4") (pintype "power_in"))
      (node (ref "X3") (pin "VBUS") (pinfunction "VBUS_VBUS") (pintype "bidirectional"))
    )
    (net (code "56") (name "unconnected-(PAD1-P-Pad1)") (class "Default")
      (node (ref "PAD1") (pin "1") (pinfunction "P_1") (pintype "passive"))
    )
    (net (code "57") (name "unconnected-(S2-Pad1)") (class "Default")
      (node (ref "S2") (pin "1") (pinfunction "1_1") (pintype "input"))
    )
    (net (code "58") (name "unconnected-(U1-P0.00{slash}AREF0-Pad17)") (class "Default")
      (node (ref "U1") (pin "17") (pinfunction "P0.00/AREF0_17") (pintype "bidirectional"))
    )
    (net (code "59") (name "unconnected-(U1-P0.01{slash}AIN2-Pad18)") (class "Default")
      (node (ref "U1") (pin "18") (pinfunction "P0.01/AIN2_18") (pintype "bidirectional"))
    )
    (net (code "60") (name "unconnected-(U1-P0.02{slash}AIN3-Pad19)") (class "Default")
      (node (ref "U1") (pin "19") (pinfunction "P0.02/AIN3_19") (pintype "bidirectional"))
    )
    (net (code "61") (name "unconnected-(U1-P0.03{slash}AIN4-Pad20)") (class "Default")
      (node (ref "U1") (pin "20") (pinfunction "P0.03/AIN4_20") (pintype "bidirectional"))
    )
    (net (code "62") (name "unconnected-(U1-P0.04{slash}AIN5-Pad21)") (class "Default")
      (node (ref "U1") (pin "21") (pinfunction "P0.04/AIN5_21") (pintype "bidirectional"))
    )
    (net (code "63") (name "unconnected-(U1-P0.05{slash}AIN6-Pad22)") (class "Default")
      (node (ref "U1") (pin "22") (pinfunction "P0.05/AIN6_22") (pintype "bidirectional"))
    )
    (net (code "64") (name "unconnected-(U1-P0.06{slash}AIN7{slash}AREF1-Pad23)") (class "Default")
      (node (ref "U1") (pin "23") (pinfunction "P0.06/AIN7/AREF1_23") (pintype "bidirectional"))
    )
    (net (code "65") (name "unconnected-(U1-P0.08-Pad26)") (class "Default")
      (node (ref "U1") (pin "26") (pinfunction "P0.08_26") (pintype "bidirectional"))
    )
    (net (code "66") (name "unconnected-(U1-P0.09-Pad27)") (class "Default")
      (node (ref "U1") (pin "27") (pinfunction "P0.09_27") (pintype "bidirectional"))
    )
    (net (code "67") (name "unconnected-(U1-P0.10-Pad28)") (class "Default")
      (node (ref "U1") (pin "28") (pinfunction "P0.10_28") (pintype "bidirectional"))
    )
    (net (code "68") (name "unconnected-(U1-P0.11-Pad29)") (class "Default")
      (node (ref "U1") (pin "29") (pinfunction "P0.11_29") (pintype "bidirectional"))
    )
    (net (code "69") (name "unconnected-(U1-P0.12-Pad30)") (class "Default")
      (node (ref "U1") (pin "30") (pinfunction "P0.12_30") (pintype "bidirectional"))
    )
    (net (code "70") (name "unconnected-(U1-P0.13-Pad31)") (class "Default")
      (node (ref "U1") (pin "31") (pinfunction "P0.13_31") (pintype "bidirectional"))
    )
    (net (code "71") (name "unconnected-(U1-P0.14-Pad32)") (class "Default")
      (node (ref "U1") (pin "32") (pinfunction "P0.14_32") (pintype "bidirectional"))
    )
    (net (code "72") (name "unconnected-(U1-P0.15-Pad33)") (class "Default")
      (node (ref "U1") (pin "33") (pinfunction "P0.15_33") (pintype "bidirectional"))
    )
    (net (code "73") (name "unconnected-(U1-P0.17-Pad37)") (class "Default")
      (node (ref "U1") (pin "37") (pinfunction "P0.17_37") (pintype "bidirectional"))
    )
    (net (code "74") (name "unconnected-(U1-P0.20-Pad40)") (class "Default")
      (node (ref "U1") (pin "40") (pinfunction "P0.20_40") (pintype "bidirectional"))
    )
    (net (code "75") (name "unconnected-(U1-P0.26{slash}AIN0{slash}XL2-Pad9)") (class "Default")
      (node (ref "U1") (pin "9") (pinfunction "P0.26/AIN0/XL2_9") (pintype "bidirectional"))
    )
    (net (code "76") (name "unconnected-(U1-P0.27{slash}AIN1{slash}XL1-Pad10)") (class "Default")
      (node (ref "U1") (pin "10") (pinfunction "P0.27/AIN1/XL1_10") (pintype "bidirectional"))
    )
    (net (code "77") (name "unconnected-(U1-P0.28-Pad11)") (class "Default")
      (node (ref "U1") (pin "11") (pinfunction "P0.28_11") (pintype "bidirectional"))
    )
    (net (code "78") (name "unconnected-(U1-P0.29-Pad12)") (class "Default")
      (node (ref "U1") (pin "12") (pinfunction "P0.29_12") (pintype "bidirectional"))
    )
    (net (code "79") (name "unconnected-(U2-P4-Pad4)") (class "Default")
      (node (ref "U2") (pin "4") (pinfunction "P4_4") (pintype "bidirectional"))
    )
    (net (code "80") (name "unconnected-(U4-PA13{slash}I13{slash}I2C{slash}SERCOM2+4.1-Pad22)") (class "Default")
      (node (ref "U4") (pin "22") (pinfunction "PA13/I13/I2C/SERCOM2+4.1_22") (pintype "bidirectional"))
    )
    (net (code "81") (name "unconnected-(U4-PA27{slash}I15-Pad39)") (class "Default")
      (node (ref "U4") (pin "39") (pinfunction "PA27/I15_39") (pintype "bidirectional"))
    )
    (net (code "82") (name "unconnected-(U4-PA28{slash}I8-Pad41)") (class "Default")
      (node (ref "U4") (pin "41") (pinfunction "PA28/I8_41") (pintype "bidirectional"))
    )
    (net (code "83") (name "unconnected-(U4-PB03{slash}I3{slash}AIN11{slash}SERCOM5.1-Pad48)") (class "Default")
      (node (ref "U4") (pin "48") (pinfunction "PB03/I3/AIN11/SERCOM5.1_48") (pintype "bidirectional"))
    )
    (net (code "84") (name "unconnected-(U4-PB22{slash}I6{slash}SERCOM5.2-Pad37)") (class "Default")
      (node (ref "U4") (pin "37") (pinfunction "PB22/I6/SERCOM5.2_37") (pintype "bidirectional"))
    )
    (net (code "85") (name "unconnected-(U4-PB23{slash}I7{slash}SERCOM5.3-Pad38)") (class "Default")
      (node (ref "U4") (pin "38") (pinfunction "PB23/I7/SERCOM5.3_38") (pintype "bidirectional"))
    )
    (net (code "86") (name "unconnected-(U25-Pad1')") (class "Default")
      (node (ref "U25") (pin "1'") (pinfunction "1'_1'") (pintype "bidirectional"))
    )
    (net (code "87") (name "unconnected-(U25-Pad2')") (class "Default")
      (node (ref "U25") (pin "2'") (pinfunction "2'_2'") (pintype "bidirectional"))
    )
    (net (code "88") (name "unconnected-(U41-Pad1')") (class "Default")
      (node (ref "U41") (pin "1'") (pinfunction "1'_1'") (pintype "bidirectional"))
    )
    (net (code "89") (name "unconnected-(U41-Pad2')") (class "Default")
      (node (ref "U41") (pin "2'") (pinfunction "2'_2'") (pintype "bidirectional"))
    )
    (net (code "90") (name "unconnected-(X3-PadID)") (class "Default")
      (node (ref "X3") (pin "ID") (pinfunction "ID_ID") (pintype "bidirectional"))
    )
  )
)
